# lab1_ignatova_usb_spi.net
KiCad netlist of a schematic drawn in Altium Designer
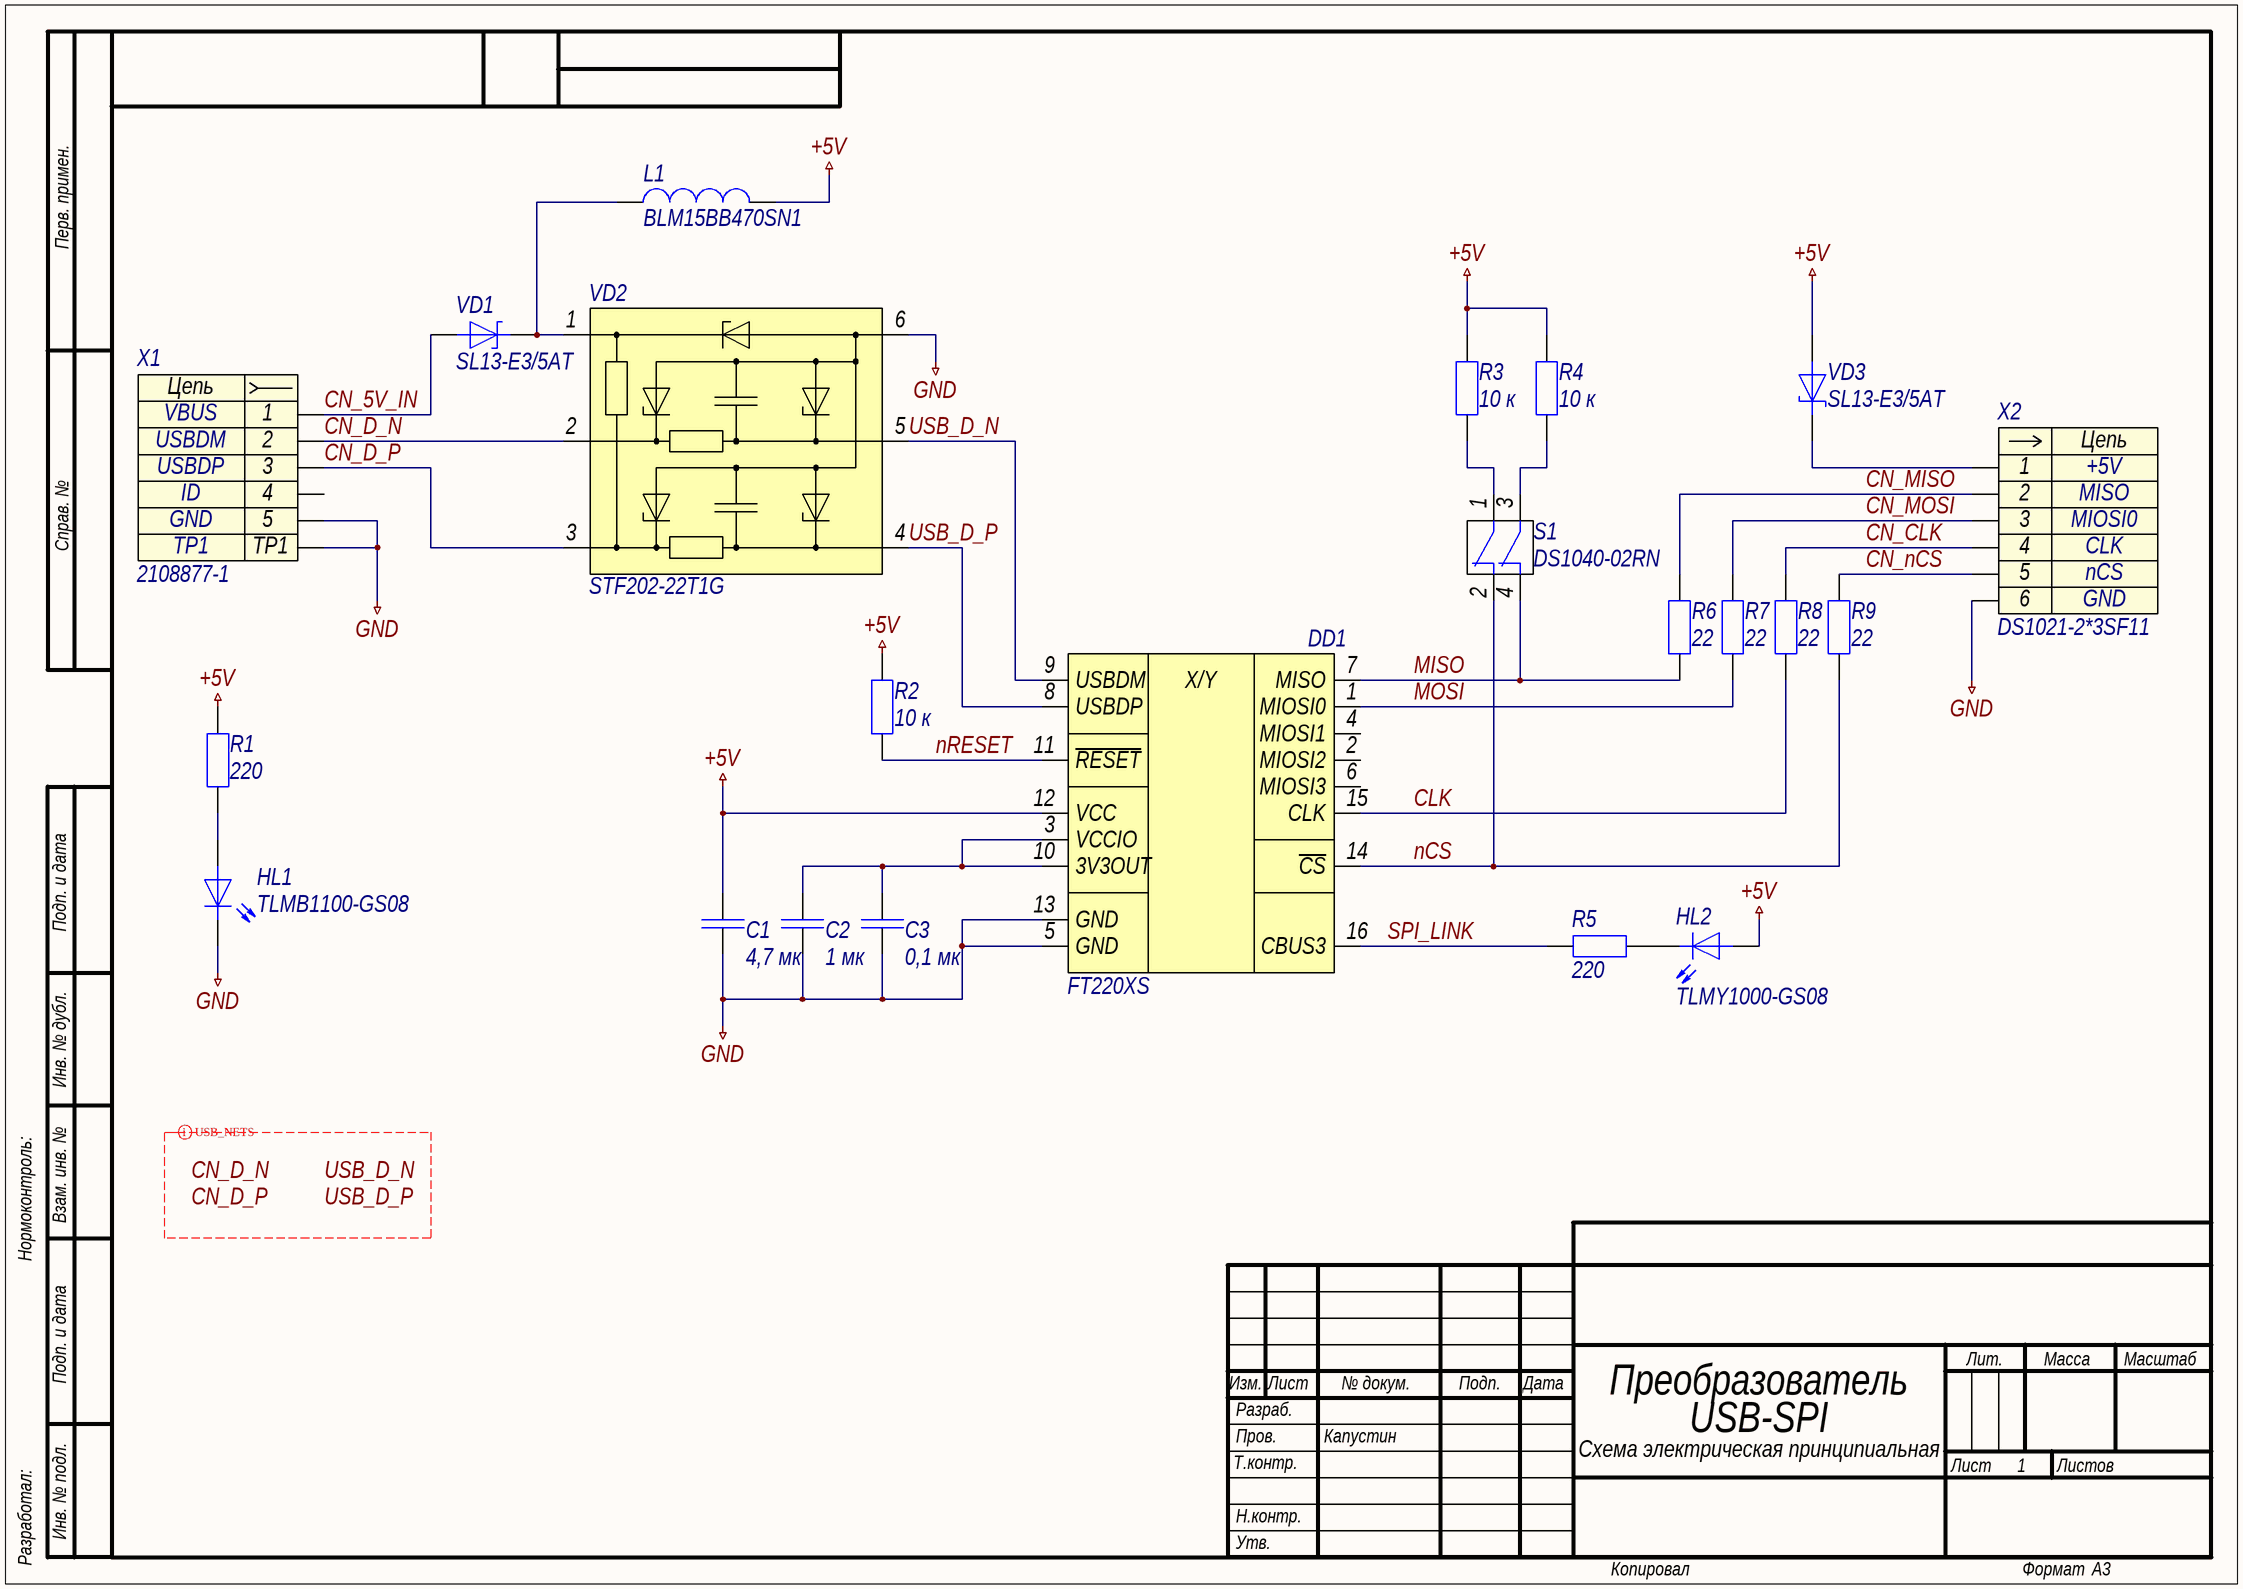
[diagram p0: lab1_ignatova_usb_spi.SchDoc]

(export (version "E")
  (design (tool "Eeschema 10.0.6"))
  (components
    (comp (ref "C1")
      (value "4,7 мк")
      (footprint "C0603")
      (description "=Описание")
      (libsource (lib "Database_Students25") (part "C-NONPOLAR"))
    )
    (comp (ref "C2")
      (value "1 мк")
      (footprint "C0603")
      (description "=Описание")
      (libsource (lib "Database_Students25") (part "C-NONPOLAR"))
    )
    (comp (ref "C3")
      (value "0,1 мк")
      (footprint "C0603")
      (description "=Описание")
      (libsource (lib "Database_Students25") (part "C-NONPOLAR"))
    )
    (comp (ref "DD1")
      (value "FT220XS")
      (footprint "SSOP-16")
      (description "=Описание")
      (libsource (lib "Database_Students") (part "FT220XS"))
    )
    (comp (ref "HL1")
      (value "TLMB1100-GS08")
      (footprint "HL0603")
      (description "=Описание")
      (libsource (lib "Database_Students25") (part "HL-COMMON"))
    )
    (comp (ref "HL2")
      (value "TLMY1000-GS08")
      (footprint "HL0603")
      (description "=Описание")
      (libsource (lib "Database_Students25") (part "HL-COMMON"))
    )
    (comp (ref "L1")
      (value "BLM15BB470SN1")
      (footprint "BLM31PG330SN1")
      (description "=Описание")
      (libsource (lib "Database_Students25") (part "I-47Ohms"))
    )
    (comp (ref "R1")
      (value "220")
      (footprint "R0603")
      (description "=Описание")
      (libsource (lib "Database_Students25") (part "R-COMMON"))
    )
    (comp (ref "R2")
      (value "10 к")
      (footprint "R0603")
      (description "=Описание")
      (libsource (lib "Database_Students25") (part "R-COMMON"))
    )
    (comp (ref "R3")
      (value "10 к")
      (footprint "R0603")
      (description "=Описание")
      (libsource (lib "Database_Students25") (part "R-COMMON"))
    )
    (comp (ref "R4")
      (value "10 к")
      (footprint "R0603")
      (description "=Описание")
      (libsource (lib "Database_Students25") (part "R-COMMON"))
    )
    (comp (ref "R5")
      (value "220")
      (footprint "R0603")
      (description "=Описание")
      (libsource (lib "Database_Students25") (part "R-COMMON"))
    )
    (comp (ref "R6")
      (value "22")
      (footprint "R0603")
      (description "=Описание")
      (libsource (lib "Database_Students25") (part "R-COMMON"))
    )
    (comp (ref "R7")
      (value "22")
      (footprint "R0603")
      (description "=Описание")
      (libsource (lib "Database_Students25") (part "R-COMMON"))
    )
    (comp (ref "R8")
      (value "22")
      (footprint "R0603")
      (description "=Описание")
      (libsource (lib "Database_Students25") (part "R-COMMON"))
    )
    (comp (ref "R9")
      (value "22")
      (footprint "R0603")
      (description "=Описание")
      (libsource (lib "Database_Students25") (part "R-COMMON"))
    )
    (comp (ref "S1")
      (value "DS1040-02RN")
      (footprint "DS1040-02RN")
      (description "=Описание")
      (libsource (lib "Database_Students") (part "SWITCH-4C"))
    )
    (comp (ref "VD1")
      (value "SL13-E3/5AT")
      (footprint "DO-214AC")
      (description "=Описание")
      (libsource (lib "") (part "DIODE-SCHOTTKY_1"))
    )
    (comp (ref "VD2")
      (value "STF202-22T1G")
      (footprint "SOT-23-6")
      (description "=Описание")
      (libsource (lib "Database_Students") (part "STF202-22T1G"))
    )
    (comp (ref "VD3")
      (value "SL13-E3/5AT")
      (footprint "DO-214AC")
      (description "=Описание")
      (libsource (lib "Database_Students25") (part "DIODE-SCHOTTKY"))
    )
    (comp (ref "X1")
      (value "2108877-1")
      (footprint "2108877-1")
      (libsource (lib "Database_Students25") (part "HEADER-5-TP1-SCT"))
    )
    (comp (ref "X2")
      (value "DS1021-2*3SF11")
      (footprint "DS1021-2X3SF11")
      (libsource (lib "Database_Students25") (part "HEADER-6-PLG"))
    )
  )
  (nets
    (net (code "1") (name "+5V") (class "Default")
      (node (ref "C1") (pin "2") (pinfunction "2_2") (pintype "passive"))
      (node (ref "DD1") (pin "12") (pinfunction "VCC_12") (pintype "passive"))
      (node (ref "HL2") (pin "2") (pinfunction "2_2") (pintype "passive"))
      (node (ref "L1") (pin "2") (pinfunction "2_2") (pintype "passive"))
      (node (ref "R1") (pin "2") (pinfunction "2_2") (pintype "passive"))
      (node (ref "R2") (pin "1") (pinfunction "1_1") (pintype "passive"))
      (node (ref "R3") (pin "2") (pinfunction "2_2") (pintype "passive"))
      (node (ref "R4") (pin "2") (pinfunction "2_2") (pintype "passive"))
      (node (ref "VD3") (pin "2") (pinfunction "2_2") (pintype "passive"))
    )
    (net (code "2") (name "/CLK") (class "Default")
      (node (ref "DD1") (pin "15") (pinfunction "CLK_15") (pintype "passive"))
      (node (ref "R8") (pin "1") (pinfunction "1_1") (pintype "passive"))
    )
    (net (code "3") (name "/CN_5V_IN") (class "Default")
      (node (ref "VD1") (pin "1") (pinfunction "1_1") (pintype "passive"))
      (node (ref "X1") (pin "1") (pinfunction "1_1") (pintype "passive"))
    )
    (net (code "4") (name "/CN_CLK") (class "Default")
      (node (ref "R8") (pin "2") (pinfunction "2_2") (pintype "passive"))
      (node (ref "X2") (pin "4") (pinfunction "4_4") (pintype "passive"))
    )
    (net (code "5") (name "/CN_D_N") (class "Default")
      (node (ref "VD2") (pin "2") (pinfunction "2_2") (pintype "passive"))
      (node (ref "X1") (pin "2") (pinfunction "2_2") (pintype "passive"))
    )
    (net (code "6") (name "/CN_D_P") (class "Default")
      (node (ref "VD2") (pin "3") (pinfunction "3_3") (pintype "passive"))
      (node (ref "X1") (pin "3") (pinfunction "3_3") (pintype "passive"))
    )
    (net (code "7") (name "/CN_MISO") (class "Default")
      (node (ref "R6") (pin "2") (pinfunction "2_2") (pintype "passive"))
      (node (ref "X2") (pin "2") (pinfunction "2_2") (pintype "passive"))
    )
    (net (code "8") (name "/CN_MOSI") (class "Default")
      (node (ref "R7") (pin "2") (pinfunction "2_2") (pintype "passive"))
      (node (ref "X2") (pin "3") (pinfunction "3_3") (pintype "passive"))
    )
    (net (code "9") (name "/CN_nCS") (class "Default")
      (node (ref "R9") (pin "2") (pinfunction "2_2") (pintype "passive"))
      (node (ref "X2") (pin "5") (pinfunction "5_5") (pintype "passive"))
    )
    (net (code "10") (name "/MISO") (class "Default")
      (node (ref "DD1") (pin "7") (pinfunction "MISO_7") (pintype "passive"))
      (node (ref "R6") (pin "1") (pinfunction "1_1") (pintype "passive"))
      (node (ref "S1") (pin "4") (pinfunction "4_4") (pintype "passive"))
    )
    (net (code "11") (name "/MOSI") (class "Default")
      (node (ref "DD1") (pin "1") (pinfunction "MIOSI0_1") (pintype "passive"))
      (node (ref "R7") (pin "1") (pinfunction "1_1") (pintype "passive"))
    )
    (net (code "12") (name "/SPI_LINK") (class "Default")
      (node (ref "DD1") (pin "16") (pinfunction "CBUS3_16") (pintype "passive"))
      (node (ref "R5") (pin "1") (pinfunction "1_1") (pintype "passive"))
    )
    (net (code "13") (name "/USB_D_N") (class "Default")
      (node (ref "DD1") (pin "9") (pinfunction "USBDM_9") (pintype "passive"))
      (node (ref "VD2") (pin "5") (pinfunction "5_5") (pintype "passive"))
    )
    (net (code "14") (name "/USB_D_P") (class "Default")
      (node (ref "DD1") (pin "8") (pinfunction "USBDP_8") (pintype "passive"))
      (node (ref "VD2") (pin "4") (pinfunction "4_4") (pintype "passive"))
    )
    (net (code "15") (name "/nCS") (class "Default")
      (node (ref "DD1") (pin "14") (pinfunction "~{CS}_14") (pintype "passive"))
      (node (ref "R9") (pin "1") (pinfunction "1_1") (pintype "passive"))
      (node (ref "S1") (pin "2") (pinfunction "2_2") (pintype "passive"))
    )
    (net (code "16") (name "/nRESET") (class "Default")
      (node (ref "DD1") (pin "11") (pinfunction "~{RESET}_11") (pintype "passive"))
      (node (ref "R2") (pin "2") (pinfunction "2_2") (pintype "passive"))
    )
    (net (code "17") (name "GND") (class "Default")
      (node (ref "C1") (pin "1") (pinfunction "1_1") (pintype "passive"))
      (node (ref "C2") (pin "1") (pinfunction "1_1") (pintype "passive"))
      (node (ref "C3") (pin "1") (pinfunction "1_1") (pintype "passive"))
      (node (ref "DD1") (pin "13") (pinfunction "GND_13") (pintype "passive"))
      (node (ref "DD1") (pin "5") (pinfunction "GND_5") (pintype "passive"))
      (node (ref "HL1") (pin "1") (pinfunction "1_1") (pintype "passive"))
      (node (ref "VD2") (pin "6") (pinfunction "6_6") (pintype "passive"))
      (node (ref "X1") (pin "5") (pinfunction "5_5") (pintype "passive"))
      (node (ref "X1") (pin "TP1") (pinfunction "TP1_TP1") (pintype "passive"))
      (node (ref "X2") (pin "6") (pinfunction "6_6") (pintype "passive"))
    )
    (net (code "18") (name "Net-(DD1-3V3OUT)") (class "Default")
      (node (ref "C2") (pin "2") (pinfunction "2_2") (pintype "passive"))
      (node (ref "C3") (pin "2") (pinfunction "2_2") (pintype "passive"))
      (node (ref "DD1") (pin "10") (pinfunction "3V3OUT_10") (pintype "passive"))
      (node (ref "DD1") (pin "3") (pinfunction "VCCIO_3") (pintype "passive"))
    )
    (net (code "19") (name "Net-(HL1-Pad2)") (class "Default")
      (node (ref "HL1") (pin "2") (pinfunction "2_2") (pintype "passive"))
      (node (ref "R1") (pin "1") (pinfunction "1_1") (pintype "passive"))
    )
    (net (code "20") (name "Net-(HL2-Pad1)") (class "Default")
      (node (ref "HL2") (pin "1") (pinfunction "1_1") (pintype "passive"))
      (node (ref "R5") (pin "2") (pinfunction "2_2") (pintype "passive"))
    )
    (net (code "21") (name "Net-(L1-Pad1)") (class "Default")
      (node (ref "L1") (pin "1") (pinfunction "1_1") (pintype "passive"))
      (node (ref "VD1") (pin "1") (pinfunction "1_1") (pintype "passive"))
      (node (ref "VD2") (pin "1") (pinfunction "1_1") (pintype "passive"))
    )
    (net (code "22") (name "Net-(R3-Pad1)") (class "Default")
      (node (ref "R3") (pin "1") (pinfunction "1_1") (pintype "passive"))
      (node (ref "S1") (pin "1") (pinfunction "1_1") (pintype "passive"))
    )
    (net (code "23") (name "Net-(R4-Pad1)") (class "Default")
      (node (ref "R4") (pin "1") (pinfunction "1_1") (pintype "passive"))
      (node (ref "S1") (pin "3") (pinfunction "3_3") (pintype "passive"))
    )
    (net (code "24") (name "Net-(VD3-Pad1)") (class "Default")
      (node (ref "VD3") (pin "1") (pinfunction "1_1") (pintype "passive"))
      (node (ref "X2") (pin "1") (pinfunction "1_1") (pintype "passive"))
    )
    (net (code "25") (name "unconnected-(DD1-MIOSI1-Pad4)") (class "Default")
      (node (ref "DD1") (pin "4") (pinfunction "MIOSI1_4") (pintype "passive"))
    )
    (net (code "26") (name "unconnected-(DD1-MIOSI2-Pad2)") (class "Default")
      (node (ref "DD1") (pin "2") (pinfunction "MIOSI2_2") (pintype "passive"))
    )
    (net (code "27") (name "unconnected-(DD1-MIOSI3-Pad6)") (class "Default")
      (node (ref "DD1") (pin "6") (pinfunction "MIOSI3_6") (pintype "passive"))
    )
    (net (code "28") (name "unconnected-(X1-Pad4)") (class "Default")
      (node (ref "X1") (pin "4") (pinfunction "4_4") (pintype "passive"))
    )
  )
)
